# shield.net
KiCad netlist of a schematic drawn in EAGLE
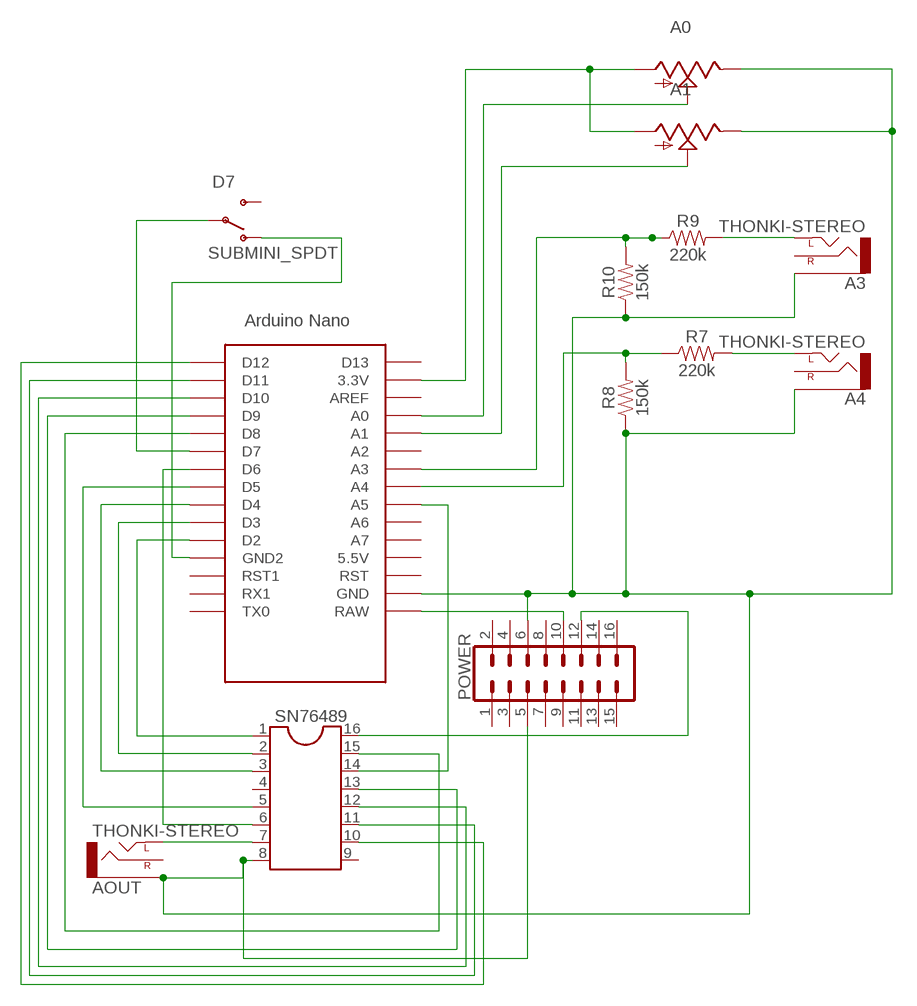
[diagram p0: schematic, sheet 1]

(export (version "E")
  (design (tool "Eeschema 10.0.6"))
  (components
    (comp (ref "A0")
      (value "9MM_SNAP-IN_POT_")
      (footprint "eagle-import:9MM_SNAP-IN_POT")
      (libsource (lib "eagle-import") (part "9MM_SNAP-IN_POT_"))
    )
    (comp (ref "A1")
      (value "9MM_SNAP-IN_POT_")
      (footprint "eagle-import:9MM_SNAP-IN_POT")
      (libsource (lib "eagle-import") (part "9MM_SNAP-IN_POT_"))
    )
    (comp (ref "A3")
      (value "THONKI-STEREO")
      (footprint "eagle-import:WQP-PJ366ST_JACK")
      (libsource (lib "eagle-import") (part "THONKI-STEREO"))
    )
    (comp (ref "A4")
      (value "THONKI-STEREO")
      (footprint "eagle-import:WQP-PJ366ST_JACK")
      (libsource (lib "eagle-import") (part "THONKI-STEREO"))
    )
    (comp (ref "AOUT")
      (value "THONKI-STEREO")
      (footprint "eagle-import:WQP-PJ366ST_JACK")
      (libsource (lib "eagle-import") (part "THONKI-STEREO"))
    )
    (comp (ref "D7")
      (value "SUBMINI_SPDT")
      (footprint "eagle-import:SUBMINI_TOGGLE")
      (libsource (lib "eagle-import") (part "SUBMINI_SPDT"))
    )
    (comp (ref "POWER")
      (value "CONN_08X2")
      (footprint "eagle-import:2X8")
      (libsource (lib "eagle-import") (part "CONN_08X2"))
    )
    (comp (ref "R7")
      (value "220k")
      (footprint "eagle-import:AXIAL-0.3-KIT")
      (libsource (lib "eagle-import") (part "100KOHM-HORIZ_KIT-1/4W-1%"))
    )
    (comp (ref "R8")
      (value "150k")
      (footprint "eagle-import:AXIAL-0.3-KIT")
      (libsource (lib "eagle-import") (part "100KOHM-HORIZ_KIT-1/4W-1%"))
    )
    (comp (ref "R9")
      (value "220k")
      (footprint "eagle-import:AXIAL-0.3-KIT")
      (libsource (lib "eagle-import") (part "100KOHM-HORIZ_KIT-1/4W-1%"))
    )
    (comp (ref "R10")
      (value "150k")
      (footprint "eagle-import:AXIAL-0.3-KIT")
      (libsource (lib "eagle-import") (part "100KOHM-HORIZ_KIT-1/4W-1%"))
    )
    (comp (ref "SN76489")
      (value "DIL16")
      (footprint "eagle-import:DIL16")
      (libsource (lib "eagle-import") (part "DIL16"))
    )
    (comp (ref "U$1")
      (value "NANO")
      (footprint "eagle-import:NANO")
      (libsource (lib "eagle-import") (part "NANO"))
    )
  )
  (nets
    (net (code "1") (name "Net-(A0-A)") (class "Default")
      (node (ref "A0") (pin "1") (pinfunction "A_1") (pintype "passive"))
      (node (ref "A1") (pin "1") (pinfunction "A_1") (pintype "passive"))
      (node (ref "U$1") (pin "3.3V") (pinfunction "3.3V_3.3V") (pintype "bidirectional"))
    )
    (net (code "2") (name "Net-(A0-E)") (class "Default")
      (node (ref "A0") (pin "3") (pinfunction "E_3") (pintype "passive"))
      (node (ref "A1") (pin "3") (pinfunction "E_3") (pintype "passive"))
      (node (ref "A3") (pin "P$3_SLEEVE") (pinfunction "SLEEVE_P$3_SLEEVE") (pintype "bidirectional"))
      (node (ref "A4") (pin "P$3_SLEEVE") (pinfunction "SLEEVE_P$3_SLEEVE") (pintype "bidirectional"))
      (node (ref "AOUT") (pin "P$3_SLEEVE") (pinfunction "SLEEVE_P$3_SLEEVE") (pintype "bidirectional"))
      (node (ref "POWER") (pin "5") (pinfunction "5_5") (pintype "passive"))
      (node (ref "POWER") (pin "6") (pinfunction "6_6") (pintype "passive"))
      (node (ref "R10") (pin "P$1") (pinfunction "1_P$1") (pintype "passive"))
      (node (ref "R8") (pin "P$1") (pinfunction "1_P$1") (pintype "passive"))
      (node (ref "SN76489") (pin "8") (pinfunction "8_8") (pintype "passive"))
      (node (ref "U$1") (pin "GND") (pinfunction "GND_GND") (pintype "bidirectional"))
    )
    (net (code "3") (name "Net-(A0-S)") (class "Default")
      (node (ref "A0") (pin "2") (pinfunction "S_2") (pintype "passive"))
      (node (ref "U$1") (pin "A0") (pinfunction "A0_A0") (pintype "bidirectional"))
    )
    (net (code "4") (name "Net-(A1-S)") (class "Default")
      (node (ref "A1") (pin "2") (pinfunction "S_2") (pintype "passive"))
      (node (ref "U$1") (pin "A1") (pinfunction "A1_A1") (pintype "bidirectional"))
    )
    (net (code "5") (name "Net-(A3-LEFT)") (class "Default")
      (node (ref "A3") (pin "P$1_TIP") (pinfunction "LEFT_P$1_TIP") (pintype "bidirectional"))
      (node (ref "R9") (pin "P$2") (pinfunction "2_P$2") (pintype "passive"))
    )
    (net (code "6") (name "Net-(A4-LEFT)") (class "Default")
      (node (ref "A4") (pin "P$1_TIP") (pinfunction "LEFT_P$1_TIP") (pintype "bidirectional"))
      (node (ref "R7") (pin "P$2") (pinfunction "2_P$2") (pintype "passive"))
    )
    (net (code "7") (name "Net-(AOUT-LEFT)") (class "Default")
      (node (ref "AOUT") (pin "P$1_TIP") (pinfunction "LEFT_P$1_TIP") (pintype "bidirectional"))
      (node (ref "SN76489") (pin "7") (pinfunction "7_7") (pintype "passive"))
    )
    (net (code "8") (name "Net-(D7-COMMON)") (class "Default")
      (node (ref "D7") (pin "COM") (pinfunction "COMMON_COM") (pintype "passive"))
      (node (ref "U$1") (pin "D7") (pinfunction "D7_D7") (pintype "bidirectional"))
    )
    (net (code "9") (name "Net-(D7-O)") (class "Default")
      (node (ref "D7") (pin "1") (pinfunction "O_1") (pintype "passive"))
      (node (ref "U$1") (pin "GND1") (pinfunction "GND2_GND1") (pintype "bidirectional"))
    )
    (net (code "10") (name "Net-(POWER-Pad10)") (class "Default")
      (node (ref "POWER") (pin "10") (pinfunction "10_10") (pintype "passive"))
      (node (ref "U$1") (pin "RAW") (pinfunction "RAW_RAW") (pintype "bidirectional"))
    )
    (net (code "11") (name "Net-(POWER-Pad12)") (class "Default")
      (node (ref "POWER") (pin "12") (pinfunction "12_12") (pintype "passive"))
      (node (ref "SN76489") (pin "16") (pinfunction "16_16") (pintype "passive"))
    )
    (net (code "12") (name "Net-(R7-1)") (class "Default")
      (node (ref "R7") (pin "P$1") (pinfunction "1_P$1") (pintype "passive"))
      (node (ref "R8") (pin "P$2") (pinfunction "2_P$2") (pintype "passive"))
      (node (ref "U$1") (pin "A4") (pinfunction "A4_A4") (pintype "bidirectional"))
    )
    (net (code "13") (name "Net-(R10-2)") (class "Default")
      (node (ref "R10") (pin "P$2") (pinfunction "2_P$2") (pintype "passive"))
      (node (ref "R9") (pin "P$1") (pinfunction "1_P$1") (pintype "passive"))
      (node (ref "U$1") (pin "A3") (pinfunction "A3_A3") (pintype "bidirectional"))
    )
    (net (code "14") (name "Net-(SN76489-Pad1)") (class "Default")
      (node (ref "SN76489") (pin "1") (pinfunction "1_1") (pintype "passive"))
      (node (ref "U$1") (pin "D2") (pinfunction "D2_D2") (pintype "bidirectional"))
    )
    (net (code "15") (name "Net-(SN76489-Pad2)") (class "Default")
      (node (ref "SN76489") (pin "2") (pinfunction "2_2") (pintype "passive"))
      (node (ref "U$1") (pin "D3") (pinfunction "D3_D3") (pintype "bidirectional"))
    )
    (net (code "16") (name "Net-(SN76489-Pad3)") (class "Default")
      (node (ref "SN76489") (pin "3") (pinfunction "3_3") (pintype "passive"))
      (node (ref "U$1") (pin "D4") (pinfunction "D4_D4") (pintype "bidirectional"))
    )
    (net (code "17") (name "Net-(SN76489-Pad5)") (class "Default")
      (node (ref "SN76489") (pin "5") (pinfunction "5_5") (pintype "passive"))
      (node (ref "U$1") (pin "D5") (pinfunction "D5_D5") (pintype "bidirectional"))
    )
    (net (code "18") (name "Net-(SN76489-Pad6)") (class "Default")
      (node (ref "SN76489") (pin "6") (pinfunction "6_6") (pintype "passive"))
      (node (ref "U$1") (pin "D6") (pinfunction "D6_D6") (pintype "bidirectional"))
    )
    (net (code "19") (name "Net-(SN76489-Pad10)") (class "Default")
      (node (ref "SN76489") (pin "10") (pinfunction "10_10") (pintype "passive"))
      (node (ref "U$1") (pin "D12") (pinfunction "D12_D12") (pintype "bidirectional"))
    )
    (net (code "20") (name "Net-(SN76489-Pad11)") (class "Default")
      (node (ref "SN76489") (pin "11") (pinfunction "11_11") (pintype "passive"))
      (node (ref "U$1") (pin "D11") (pinfunction "D11_D11") (pintype "bidirectional"))
    )
    (net (code "21") (name "Net-(SN76489-Pad12)") (class "Default")
      (node (ref "SN76489") (pin "12") (pinfunction "12_12") (pintype "passive"))
      (node (ref "U$1") (pin "D10") (pinfunction "D10_D10") (pintype "bidirectional"))
    )
    (net (code "22") (name "Net-(SN76489-Pad13)") (class "Default")
      (node (ref "SN76489") (pin "13") (pinfunction "13_13") (pintype "passive"))
      (node (ref "U$1") (pin "D9") (pinfunction "D9_D9") (pintype "bidirectional"))
    )
    (net (code "23") (name "Net-(SN76489-Pad14)") (class "Default")
      (node (ref "SN76489") (pin "14") (pinfunction "14_14") (pintype "passive"))
      (node (ref "U$1") (pin "A5") (pinfunction "A5_A5") (pintype "bidirectional"))
    )
    (net (code "24") (name "Net-(SN76489-Pad15)") (class "Default")
      (node (ref "SN76489") (pin "15") (pinfunction "15_15") (pintype "passive"))
      (node (ref "U$1") (pin "D8") (pinfunction "D8_D8") (pintype "bidirectional"))
    )
    (net (code "25") (name "unconnected-(A3-RIGHT-PadP$2_SWITCH)") (class "Default")
      (node (ref "A3") (pin "P$2_SWITCH") (pinfunction "RIGHT_P$2_SWITCH") (pintype "bidirectional"))
    )
    (net (code "26") (name "unconnected-(A4-RIGHT-PadP$2_SWITCH)") (class "Default")
      (node (ref "A4") (pin "P$2_SWITCH") (pinfunction "RIGHT_P$2_SWITCH") (pintype "bidirectional"))
    )
    (net (code "27") (name "unconnected-(AOUT-RIGHT-PadP$2_SWITCH)") (class "Default")
      (node (ref "AOUT") (pin "P$2_SWITCH") (pinfunction "RIGHT_P$2_SWITCH") (pintype "bidirectional"))
    )
    (net (code "28") (name "unconnected-(D7-S-Pad3)") (class "Default")
      (node (ref "D7") (pin "3") (pinfunction "S_3") (pintype "passive"))
    )
    (net (code "29") (name "unconnected-(POWER-Pad1)") (class "Default")
      (node (ref "POWER") (pin "1") (pinfunction "1_1") (pintype "passive"))
    )
    (net (code "30") (name "unconnected-(POWER-Pad2)") (class "Default")
      (node (ref "POWER") (pin "2") (pinfunction "2_2") (pintype "passive"))
    )
    (net (code "31") (name "unconnected-(POWER-Pad3)") (class "Default")
      (node (ref "POWER") (pin "3") (pinfunction "3_3") (pintype "passive"))
    )
    (net (code "32") (name "unconnected-(POWER-Pad4)") (class "Default")
      (node (ref "POWER") (pin "4") (pinfunction "4_4") (pintype "passive"))
    )
    (net (code "33") (name "unconnected-(POWER-Pad7)") (class "Default")
      (node (ref "POWER") (pin "7") (pinfunction "7_7") (pintype "passive"))
    )
    (net (code "34") (name "unconnected-(POWER-Pad8)") (class "Default")
      (node (ref "POWER") (pin "8") (pinfunction "8_8") (pintype "passive"))
    )
    (net (code "35") (name "unconnected-(POWER-Pad9)") (class "Default")
      (node (ref "POWER") (pin "9") (pinfunction "9_9") (pintype "passive"))
    )
    (net (code "36") (name "unconnected-(POWER-Pad11)") (class "Default")
      (node (ref "POWER") (pin "11") (pinfunction "11_11") (pintype "passive"))
    )
    (net (code "37") (name "unconnected-(POWER-Pad13)") (class "Default")
      (node (ref "POWER") (pin "13") (pinfunction "13_13") (pintype "passive"))
    )
    (net (code "38") (name "unconnected-(POWER-Pad14)") (class "Default")
      (node (ref "POWER") (pin "14") (pinfunction "14_14") (pintype "passive"))
    )
    (net (code "39") (name "unconnected-(POWER-Pad15)") (class "Default")
      (node (ref "POWER") (pin "15") (pinfunction "15_15") (pintype "passive"))
    )
    (net (code "40") (name "unconnected-(POWER-Pad16)") (class "Default")
      (node (ref "POWER") (pin "16") (pinfunction "16_16") (pintype "passive"))
    )
    (net (code "41") (name "unconnected-(SN76489-Pad4)") (class "Default")
      (node (ref "SN76489") (pin "4") (pinfunction "4_4") (pintype "passive"))
    )
    (net (code "42") (name "unconnected-(SN76489-Pad9)") (class "Default")
      (node (ref "SN76489") (pin "9") (pinfunction "9_9") (pintype "passive"))
    )
    (net (code "43") (name "unconnected-(U$1-5.5V-Pad5V)") (class "Default")
      (node (ref "U$1") (pin "5V") (pinfunction "5.5V_5V") (pintype "bidirectional"))
    )
    (net (code "44") (name "unconnected-(U$1-PadA2)") (class "Default")
      (node (ref "U$1") (pin "A2") (pinfunction "A2_A2") (pintype "bidirectional"))
    )
    (net (code "45") (name "unconnected-(U$1-PadA6)") (class "Default")
      (node (ref "U$1") (pin "A6") (pinfunction "A6_A6") (pintype "bidirectional"))
    )
    (net (code "46") (name "unconnected-(U$1-PadA7)") (class "Default")
      (node (ref "U$1") (pin "A7") (pinfunction "A7_A7") (pintype "bidirectional"))
    )
    (net (code "47") (name "unconnected-(U$1-PadAREF)") (class "Default")
      (node (ref "U$1") (pin "AREF") (pinfunction "AREF_AREF") (pintype "bidirectional"))
    )
    (net (code "48") (name "unconnected-(U$1-PadD13)") (class "Default")
      (node (ref "U$1") (pin "D13") (pinfunction "D13_D13") (pintype "bidirectional"))
    )
    (net (code "49") (name "unconnected-(U$1-PadICSP1)") (class "Default")
      (node (ref "U$1") (pin "ICSP1") (pinfunction "ICSP1_ICSP1") (pintype "bidirectional"))
    )
    (net (code "50") (name "unconnected-(U$1-PadICSP2)") (class "Default")
      (node (ref "U$1") (pin "ICSP2") (pinfunction "ICSP2_ICSP2") (pintype "bidirectional"))
    )
    (net (code "51") (name "unconnected-(U$1-PadICSP3)") (class "Default")
      (node (ref "U$1") (pin "ICSP3") (pinfunction "ICSP3_ICSP3") (pintype "bidirectional"))
    )
    (net (code "52") (name "unconnected-(U$1-PadICSP4)") (class "Default")
      (node (ref "U$1") (pin "ICSP4") (pinfunction "ICSP4_ICSP4") (pintype "bidirectional"))
    )
    (net (code "53") (name "unconnected-(U$1-PadICSP5)") (class "Default")
      (node (ref "U$1") (pin "ICSP5") (pinfunction "ICSP5_ICSP5") (pintype "bidirectional"))
    )
    (net (code "54") (name "unconnected-(U$1-PadICSP6)") (class "Default")
      (node (ref "U$1") (pin "ICSP6") (pinfunction "ICSP6_ICSP6") (pintype "bidirectional"))
    )
    (net (code "55") (name "unconnected-(U$1-PadRST)") (class "Default")
      (node (ref "U$1") (pin "RST") (pinfunction "RST_RST") (pintype "bidirectional"))
    )
    (net (code "56") (name "unconnected-(U$1-PadRST1)") (class "Default")
      (node (ref "U$1") (pin "RST1") (pinfunction "RST1_RST1") (pintype "bidirectional"))
    )
    (net (code "57") (name "unconnected-(U$1-PadRX1)") (class "Default")
      (node (ref "U$1") (pin "RX1") (pinfunction "RX1_RX1") (pintype "bidirectional"))
    )
    (net (code "58") (name "unconnected-(U$1-PadTX0)") (class "Default")
      (node (ref "U$1") (pin "TX0") (pinfunction "TX0_TX0") (pintype "bidirectional"))
    )
  )
)
